# mssaPIC16.net
KiCad netlist of a schematic drawn in EAGLE
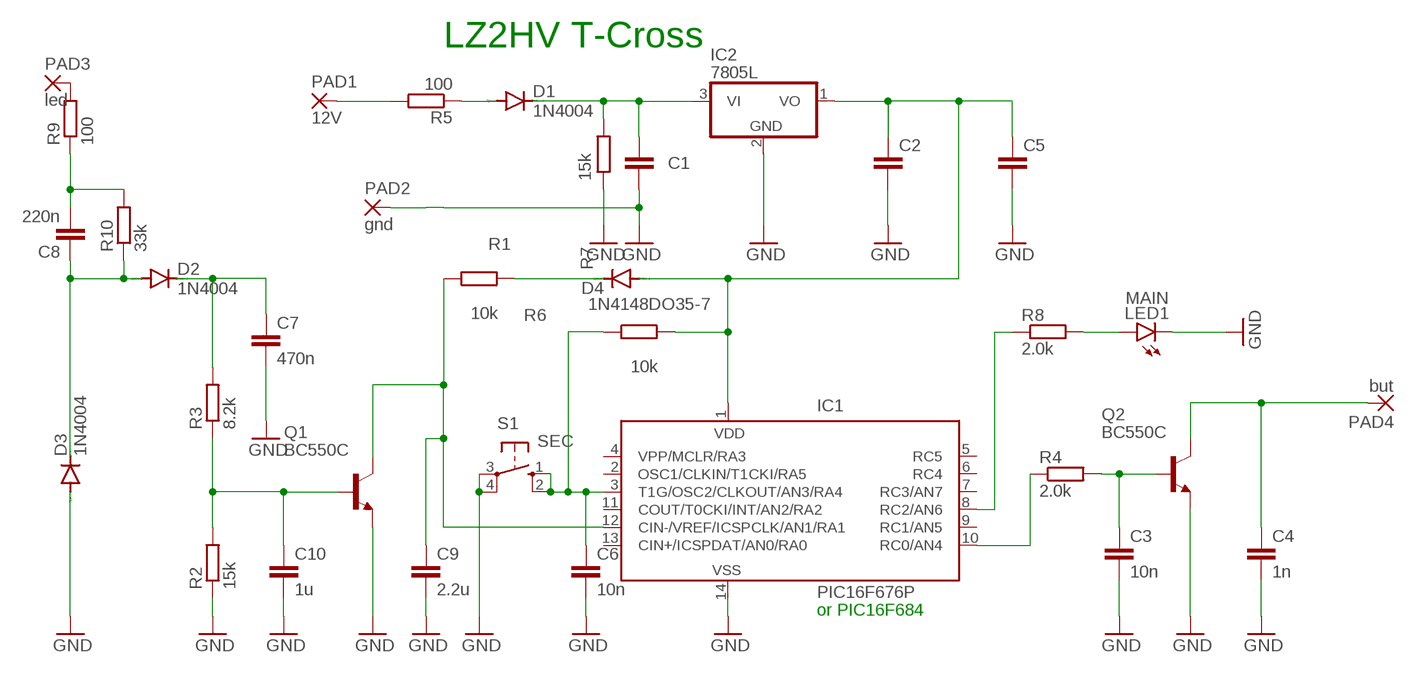
[diagram p0: schematic, sheet 1]

(export (version "E")
  (design (tool "Eeschema 10.0.6"))
  (components
    (comp (ref "C1")
      (value "100n")
      (footprint "eagle-import:C5B2.5")
      (libsource (lib "eagle-import") (part "C5/2.5"))
    )
    (comp (ref "C2")
      (value "101n")
      (footprint "eagle-import:C5B2.5")
      (libsource (lib "eagle-import") (part "C5/2.5"))
    )
    (comp (ref "C3")
      (value "10n")
      (footprint "eagle-import:C5B2.5")
      (libsource (lib "eagle-import") (part "C5/2.5"))
    )
    (comp (ref "C4")
      (value "1n")
      (footprint "eagle-import:C5B2.5")
      (libsource (lib "eagle-import") (part "C5/2.5"))
    )
    (comp (ref "C5")
      (value "220n")
      (footprint "eagle-import:C5B2.5")
      (libsource (lib "eagle-import") (part "C5/2.5"))
    )
    (comp (ref "C6")
      (value "10n")
      (footprint "eagle-import:C5B2.5")
      (libsource (lib "eagle-import") (part "C5/2.5"))
    )
    (comp (ref "C7")
      (value "470n")
      (footprint "eagle-import:C5B2.5")
      (libsource (lib "eagle-import") (part "C5/2.5"))
    )
    (comp (ref "C8")
      (value "220n")
      (footprint "eagle-import:C5B2.5")
      (libsource (lib "eagle-import") (part "C5/2.5"))
    )
    (comp (ref "C9")
      (value "2.2u")
      (footprint "eagle-import:C5B2.5")
      (libsource (lib "eagle-import") (part "C5/2.5"))
    )
    (comp (ref "C10")
      (value "1u")
      (footprint "eagle-import:C5B2.5")
      (libsource (lib "eagle-import") (part "C5/2.5"))
    )
    (comp (ref "D1")
      (value "1N4004")
      (footprint "eagle-import:DO41-10")
      (libsource (lib "eagle-import") (part "1N4004"))
    )
    (comp (ref "D2")
      (value "1N4004")
      (footprint "eagle-import:DO41-10")
      (libsource (lib "eagle-import") (part "1N4004"))
    )
    (comp (ref "D3")
      (value "1N4004")
      (footprint "eagle-import:DO41-10")
      (libsource (lib "eagle-import") (part "1N4004"))
    )
    (comp (ref "D4")
      (value "1N4148DO35-7")
      (footprint "eagle-import:DO35-7")
      (libsource (lib "eagle-import") (part "1N4148DO35-7"))
    )
    (comp (ref "IC1")
      (value "PIC16F676P")
      (footprint "eagle-import:DIL14")
      (fields (field (name "MF") "MICROCHIP") (field (name "MPN") "PIC16F676-I/P"))
      (libsource (lib "eagle-import") (part "PIC16F676P"))
    )
    (comp (ref "IC2")
      (value "7805L")
      (footprint "eagle-import:TO92")
      (libsource (lib "eagle-import") (part "78L05"))
    )
    (comp (ref "LED1")
      (value "MAIN")
      (footprint "eagle-import:LED3MM")
      (libsource (lib "eagle-import") (part "LED3MM"))
    )
    (comp (ref "PAD1")
      (value "12V")
      (footprint "eagle-import:2,54_1,0")
      (libsource (lib "eagle-import") (part "2,54/1,0"))
    )
    (comp (ref "PAD2")
      (value "gnd")
      (footprint "eagle-import:2,54_1,0")
      (libsource (lib "eagle-import") (part "2,54/1,0"))
    )
    (comp (ref "PAD3")
      (value "led")
      (footprint "eagle-import:2,54_1,0")
      (libsource (lib "eagle-import") (part "2,54/1,0"))
    )
    (comp (ref "PAD4")
      (value "but")
      (footprint "eagle-import:2,54_1,0")
      (libsource (lib "eagle-import") (part "2,54/1,0"))
    )
    (comp (ref "Q1")
      (value "BC550C")
      (footprint "eagle-import:TO92-EBC")
      (libsource (lib "eagle-import") (part "BC550C"))
    )
    (comp (ref "Q2")
      (value "BC550C")
      (footprint "eagle-import:TO92-EBC")
      (libsource (lib "eagle-import") (part "BC550C"))
    )
    (comp (ref "R1")
      (value "10k")
      (footprint "eagle-import:0207_7")
      (libsource (lib "eagle-import") (part "R-EU_0207/7"))
    )
    (comp (ref "R2")
      (value "15k")
      (footprint "eagle-import:0207_7")
      (libsource (lib "eagle-import") (part "R-EU_0207/7"))
    )
    (comp (ref "R3")
      (value "8.2k")
      (footprint "eagle-import:0207_7")
      (libsource (lib "eagle-import") (part "R-EU_0207/7"))
    )
    (comp (ref "R4")
      (value "2.0k")
      (footprint "eagle-import:0207_7")
      (libsource (lib "eagle-import") (part "R-EU_0207/7"))
    )
    (comp (ref "R5")
      (value "100")
      (footprint "eagle-import:0207_7")
      (libsource (lib "eagle-import") (part "R-EU_0207/7"))
    )
    (comp (ref "R6")
      (value "10k")
      (footprint "eagle-import:0207_7")
      (libsource (lib "eagle-import") (part "R-EU_0207/7"))
    )
    (comp (ref "R7")
      (value "15k")
      (footprint "eagle-import:0207_7")
      (libsource (lib "eagle-import") (part "R-EU_0207/7"))
    )
    (comp (ref "R8")
      (value "2.0k")
      (footprint "eagle-import:0207_7")
      (libsource (lib "eagle-import") (part "R-EU_0207/7"))
    )
    (comp (ref "R9")
      (value "100")
      (footprint "eagle-import:0207_2V")
      (libsource (lib "eagle-import") (part "R-EU_0207/2V"))
    )
    (comp (ref "R10")
      (value "33k")
      (footprint "eagle-import:0207_2V")
      (libsource (lib "eagle-import") (part "R-EU_0207/2V"))
    )
    (comp (ref "S1")
      (value "SEC")
      (footprint "eagle-import:B3F-10XX")
      (fields (field (name "MPN") "B3F-1000"))
      (libsource (lib "eagle-import") (part "10-XX"))
    )
  )
  (nets
    (net (code "1") (name "GND") (class "Default")
      (node (ref "C1") (pin "2") (pinfunction "2_2") (pintype "passive"))
      (node (ref "C10") (pin "2") (pinfunction "2_2") (pintype "passive"))
      (node (ref "C2") (pin "2") (pinfunction "2_2") (pintype "passive"))
      (node (ref "C3") (pin "2") (pinfunction "2_2") (pintype "passive"))
      (node (ref "C4") (pin "2") (pinfunction "2_2") (pintype "passive"))
      (node (ref "C5") (pin "2") (pinfunction "2_2") (pintype "passive"))
      (node (ref "C6") (pin "2") (pinfunction "2_2") (pintype "passive"))
      (node (ref "C7") (pin "2") (pinfunction "2_2") (pintype "passive"))
      (node (ref "C9") (pin "2") (pinfunction "2_2") (pintype "passive"))
      (node (ref "D3") (pin "A") (pinfunction "A_A") (pintype "passive"))
      (node (ref "IC1") (pin "14") (pinfunction "VSS_14") (pintype "power_in"))
      (node (ref "IC2") (pin "2") (pinfunction "GND_2") (pintype "passive"))
      (node (ref "LED1") (pin "K") (pinfunction "C_K") (pintype "passive"))
      (node (ref "PAD2") (pin "1") (pinfunction "P_1") (pintype "passive"))
      (node (ref "Q1") (pin "E") (pinfunction "E_E") (pintype "passive"))
      (node (ref "Q2") (pin "E") (pinfunction "E_E") (pintype "passive"))
      (node (ref "R2") (pin "1") (pinfunction "1_1") (pintype "passive"))
      (node (ref "R7") (pin "1") (pinfunction "1_1") (pintype "passive"))
      (node (ref "S1") (pin "3") (pinfunction "P_3") (pintype "passive"))
      (node (ref "S1") (pin "4") (pinfunction "P1_4") (pintype "passive"))
    )
    (net (code "2") (name "Net-(C3-Pad1)") (class "Default")
      (node (ref "C3") (pin "1") (pinfunction "1_1") (pintype "passive"))
      (node (ref "Q2") (pin "B") (pinfunction "B_B") (pintype "passive"))
      (node (ref "R4") (pin "2") (pinfunction "2_2") (pintype "passive"))
    )
    (net (code "3") (name "Net-(C7-Pad1)") (class "Default")
      (node (ref "C7") (pin "1") (pinfunction "1_1") (pintype "passive"))
      (node (ref "D2") (pin "C") (pinfunction "C_C") (pintype "passive"))
      (node (ref "R3") (pin "2") (pinfunction "2_2") (pintype "passive"))
    )
    (net (code "4") (name "Net-(C8-Pad1)") (class "Default")
      (node (ref "C8") (pin "1") (pinfunction "1_1") (pintype "passive"))
      (node (ref "D2") (pin "A") (pinfunction "A_A") (pintype "passive"))
      (node (ref "D3") (pin "C") (pinfunction "C_C") (pintype "passive"))
      (node (ref "R10") (pin "1") (pinfunction "1_1") (pintype "passive"))
    )
    (net (code "5") (name "Net-(C8-Pad2)") (class "Default")
      (node (ref "C8") (pin "2") (pinfunction "2_2") (pintype "passive"))
      (node (ref "R10") (pin "2") (pinfunction "2_2") (pintype "passive"))
      (node (ref "R9") (pin "1") (pinfunction "1_1") (pintype "passive"))
    )
    (net (code "6") (name "Net-(C10-Pad1)") (class "Default")
      (node (ref "C10") (pin "1") (pinfunction "1_1") (pintype "passive"))
      (node (ref "Q1") (pin "B") (pinfunction "B_B") (pintype "passive"))
      (node (ref "R2") (pin "2") (pinfunction "2_2") (pintype "passive"))
      (node (ref "R3") (pin "1") (pinfunction "1_1") (pintype "passive"))
    )
    (net (code "7") (name "Net-(D1-PadA)") (class "Default")
      (node (ref "D1") (pin "A") (pinfunction "A_A") (pintype "passive"))
      (node (ref "R5") (pin "1") (pinfunction "1_1") (pintype "passive"))
    )
    (net (code "8") (name "Net-(D4-PadC)") (class "Default")
      (node (ref "D4") (pin "C") (pinfunction "C_C") (pintype "passive"))
      (node (ref "R1") (pin "2") (pinfunction "2_2") (pintype "passive"))
    )
    (net (code "9") (name "Net-(IC1-CIN-{slash}VREF{slash}ICSPCLK{slash}AN1{slash}RA1)") (class "Default")
      (node (ref "C9") (pin "1") (pinfunction "1_1") (pintype "passive"))
      (node (ref "IC1") (pin "12") (pinfunction "CIN-/VREF/ICSPCLK/AN1/RA1_12") (pintype "bidirectional"))
      (node (ref "Q1") (pin "C") (pinfunction "C_C") (pintype "passive"))
      (node (ref "R1") (pin "1") (pinfunction "1_1") (pintype "passive"))
    )
    (net (code "10") (name "Net-(IC1-RC0{slash}AN4)") (class "Default")
      (node (ref "IC1") (pin "10") (pinfunction "RC0/AN4_10") (pintype "bidirectional"))
      (node (ref "R4") (pin "1") (pinfunction "1_1") (pintype "passive"))
    )
    (net (code "11") (name "Net-(IC1-RC2{slash}AN6)") (class "Default")
      (node (ref "IC1") (pin "8") (pinfunction "RC2/AN6_8") (pintype "bidirectional"))
      (node (ref "R8") (pin "1") (pinfunction "1_1") (pintype "passive"))
    )
    (net (code "12") (name "Net-(IC1-T1G{slash}OSC2{slash}CLKOUT{slash}AN3{slash}RA4)") (class "Default")
      (node (ref "C6") (pin "1") (pinfunction "1_1") (pintype "passive"))
      (node (ref "IC1") (pin "3") (pinfunction "T1G/OSC2/CLKOUT/AN3/RA4_3") (pintype "bidirectional"))
      (node (ref "R6") (pin "1") (pinfunction "1_1") (pintype "passive"))
      (node (ref "S1") (pin "1") (pinfunction "S_1") (pintype "passive"))
      (node (ref "S1") (pin "2") (pinfunction "S1_2") (pintype "passive"))
    )
    (net (code "13") (name "Net-(IC1-VDD)") (class "Default")
      (node (ref "C2") (pin "1") (pinfunction "1_1") (pintype "passive"))
      (node (ref "C5") (pin "1") (pinfunction "1_1") (pintype "passive"))
      (node (ref "D4") (pin "A") (pinfunction "A_A") (pintype "passive"))
      (node (ref "IC1") (pin "1") (pinfunction "VDD_1") (pintype "power_in"))
      (node (ref "IC2") (pin "1") (pinfunction "VO_1") (pintype "passive"))
      (node (ref "R6") (pin "2") (pinfunction "2_2") (pintype "passive"))
    )
    (net (code "14") (name "Net-(IC2-VI)") (class "Default")
      (node (ref "C1") (pin "1") (pinfunction "1_1") (pintype "passive"))
      (node (ref "D1") (pin "C") (pinfunction "C_C") (pintype "passive"))
      (node (ref "IC2") (pin "3") (pinfunction "VI_3") (pintype "input"))
      (node (ref "R7") (pin "2") (pinfunction "2_2") (pintype "passive"))
    )
    (net (code "15") (name "Net-(LED1-PadA)") (class "Default")
      (node (ref "LED1") (pin "A") (pinfunction "A_A") (pintype "passive"))
      (node (ref "R8") (pin "2") (pinfunction "2_2") (pintype "passive"))
    )
    (net (code "16") (name "Net-(PAD1-P)") (class "Default")
      (node (ref "PAD1") (pin "1") (pinfunction "P_1") (pintype "passive"))
      (node (ref "R5") (pin "2") (pinfunction "2_2") (pintype "passive"))
    )
    (net (code "17") (name "Net-(PAD3-P)") (class "Default")
      (node (ref "PAD3") (pin "1") (pinfunction "P_1") (pintype "passive"))
      (node (ref "R9") (pin "2") (pinfunction "2_2") (pintype "passive"))
    )
    (net (code "18") (name "Net-(PAD4-P)") (class "Default")
      (node (ref "C4") (pin "1") (pinfunction "1_1") (pintype "passive"))
      (node (ref "PAD4") (pin "1") (pinfunction "P_1") (pintype "passive"))
      (node (ref "Q2") (pin "C") (pinfunction "C_C") (pintype "passive"))
    )
    (net (code "19") (name "unconnected-(IC1-CIN+{slash}ICSPDAT{slash}AN0{slash}RA0-Pad13)") (class "Default")
      (node (ref "IC1") (pin "13") (pinfunction "CIN+/ICSPDAT/AN0/RA0_13") (pintype "bidirectional"))
    )
    (net (code "20") (name "unconnected-(IC1-COUT{slash}T0CKI{slash}INT{slash}AN2{slash}RA2-Pad11)") (class "Default")
      (node (ref "IC1") (pin "11") (pinfunction "COUT/T0CKI/INT/AN2/RA2_11") (pintype "bidirectional"))
    )
    (net (code "21") (name "unconnected-(IC1-OSC1{slash}CLKIN{slash}T1CKI{slash}RA5-Pad2)") (class "Default")
      (node (ref "IC1") (pin "2") (pinfunction "OSC1/CLKIN/T1CKI/RA5_2") (pintype "bidirectional"))
    )
    (net (code "22") (name "unconnected-(IC1-RC1{slash}AN5-Pad9)") (class "Default")
      (node (ref "IC1") (pin "9") (pinfunction "RC1/AN5_9") (pintype "bidirectional"))
    )
    (net (code "23") (name "unconnected-(IC1-RC3{slash}AN7-Pad7)") (class "Default")
      (node (ref "IC1") (pin "7") (pinfunction "RC3/AN7_7") (pintype "bidirectional"))
    )
    (net (code "24") (name "unconnected-(IC1-RC4-Pad6)") (class "Default")
      (node (ref "IC1") (pin "6") (pinfunction "RC4_6") (pintype "bidirectional"))
    )
    (net (code "25") (name "unconnected-(IC1-RC5-Pad5)") (class "Default")
      (node (ref "IC1") (pin "5") (pinfunction "RC5_5") (pintype "bidirectional"))
    )
    (net (code "26") (name "unconnected-(IC1-VPP{slash}MCLR{slash}RA3-Pad4)") (class "Default")
      (node (ref "IC1") (pin "4") (pinfunction "VPP/MCLR/RA3_4") (pintype "input"))
    )
  )
)
